# Battery_Voltage_Monitor.net
KiCad netlist of a schematic drawn in Altium Designer
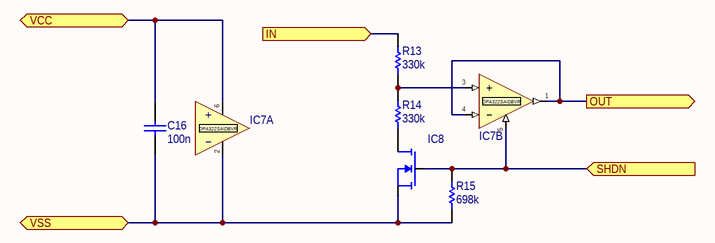
[diagram p0: Battery Voltage Monitor.SchDoc]

(export (version "E")
  (design (tool "Eeschema 10.0.6"))
  (components
    (comp (ref "C16")
      (value "100n")
      (footprint "C0603")
      (description "Cap, 100n, 0603, X7R, 50V")
      (fields (field (name "MANUFACTURER") "Yageo") (field (name "MPN") "CC0603KRX7R9BB104"))
      (libsource (lib "Createc Circuitstudio Library") (part "CC0603KRX7R9BB104"))
    )
    (comp (ref "IC7")
      (value "OPA322SAIDBVR")
      (footprint "SOT-23-6")
      (description "Op-Amp, SOT-32, 1.7-5.5V, Rail-to-rail, Nanopower")
      (fields (field (name "MANUFACTURER") "Texas Instruments"))
      (libsource (lib "Schlib1") (part "OPA322SAIDBVR"))
    )
    (comp (ref "IC8")
      (value "PMZ600UNEL")
      (footprint "SOT-883")
      (description "MOSFET, SOT-883, n-channel, 20V, 0.6A, low leakage current")
      (fields (field (name "MANUFACTURER") "Nexperia"))
      (libsource (lib "Schlib1") (part "PMZ600UNEL"))
    )
    (comp (ref "R13")
      (value "330k")
      (footprint "R0603")
      (description "Res, 330k, 0603, 0.1%, 25ppm, 75V, 100mW")
      (fields (field (name "TOLERANCE") "0.1%") (field (name "MPN") "ERA-3AEB334V"))
      (libsource (lib "Schlib1") (part "ERA-3AEB334V"))
    )
    (comp (ref "R14")
      (value "330k")
      (footprint "R0603")
      (description "Res, 330k, 0603, 0.1%, 25ppm, 75V, 100mW")
      (fields (field (name "TOLERANCE") "0.1%") (field (name "MPN") "ERA-3AEB334V"))
      (libsource (lib "Schlib1") (part "ERA-3AEB334V"))
    )
    (comp (ref "R15")
      (value "698k")
      (footprint "R0603")
      (description "Res, 698k, 0603, 1%, 75V, 100mW")
      (fields (field (name "TOLERANCE") "1%") (field (name "MPN") "ERJ-3EKF6983V"))
      (libsource (lib "Schlib1") (part "ERJ-3EKF6983V"))
    )
  )
  (nets
    (net (code "1") (name "/IN") (class "Default")
      (node (ref "R13") (pin "2") (pinfunction "2_2") (pintype "passive"))
    )
    (net (code "2") (name "/OUT") (class "Default")
      (node (ref "IC7") (pin "1") (pinfunction "Out_1") (pintype "output"))
      (node (ref "IC7") (pin "4") (pinfunction "−_4") (pintype "input"))
    )
    (net (code "3") (name "/SHDN") (class "Default")
      (node (ref "IC7") (pin "5") (pinfunction "~{SHDN}_5") (pintype "input"))
      (node (ref "IC8") (pin "1") (pinfunction "G_1") (pintype "passive"))
      (node (ref "R15") (pin "2") (pinfunction "2_2") (pintype "passive"))
    )
    (net (code "4") (name "/VCC") (class "Default")
      (node (ref "C16") (pin "2") (pinfunction "2_2") (pintype "passive"))
      (node (ref "IC7") (pin "6") (pinfunction "+_6") (pintype "passive"))
    )
    (net (code "5") (name "/VSS") (class "Default")
      (node (ref "C16") (pin "1") (pinfunction "1_1") (pintype "passive"))
      (node (ref "IC7") (pin "2") (pinfunction "-_2") (pintype "passive"))
      (node (ref "IC8") (pin "2") (pinfunction "S_2") (pintype "passive"))
      (node (ref "R15") (pin "1") (pinfunction "1_1") (pintype "passive"))
    )
    (net (code "6") (name "Net-(IC7B-+)") (class "Default")
      (node (ref "IC7") (pin "3") (pinfunction "+_3") (pintype "input"))
      (node (ref "R13") (pin "1") (pinfunction "1_1") (pintype "passive"))
      (node (ref "R14") (pin "2") (pinfunction "2_2") (pintype "passive"))
    )
    (net (code "7") (name "Net-(IC8-D)") (class "Default")
      (node (ref "IC8") (pin "3") (pinfunction "D_3") (pintype "passive"))
      (node (ref "R14") (pin "1") (pinfunction "1_1") (pintype "passive"))
    )
  )
)
